# picoslidertoy.net
KiCad netlist of a schematic drawn in EAGLE
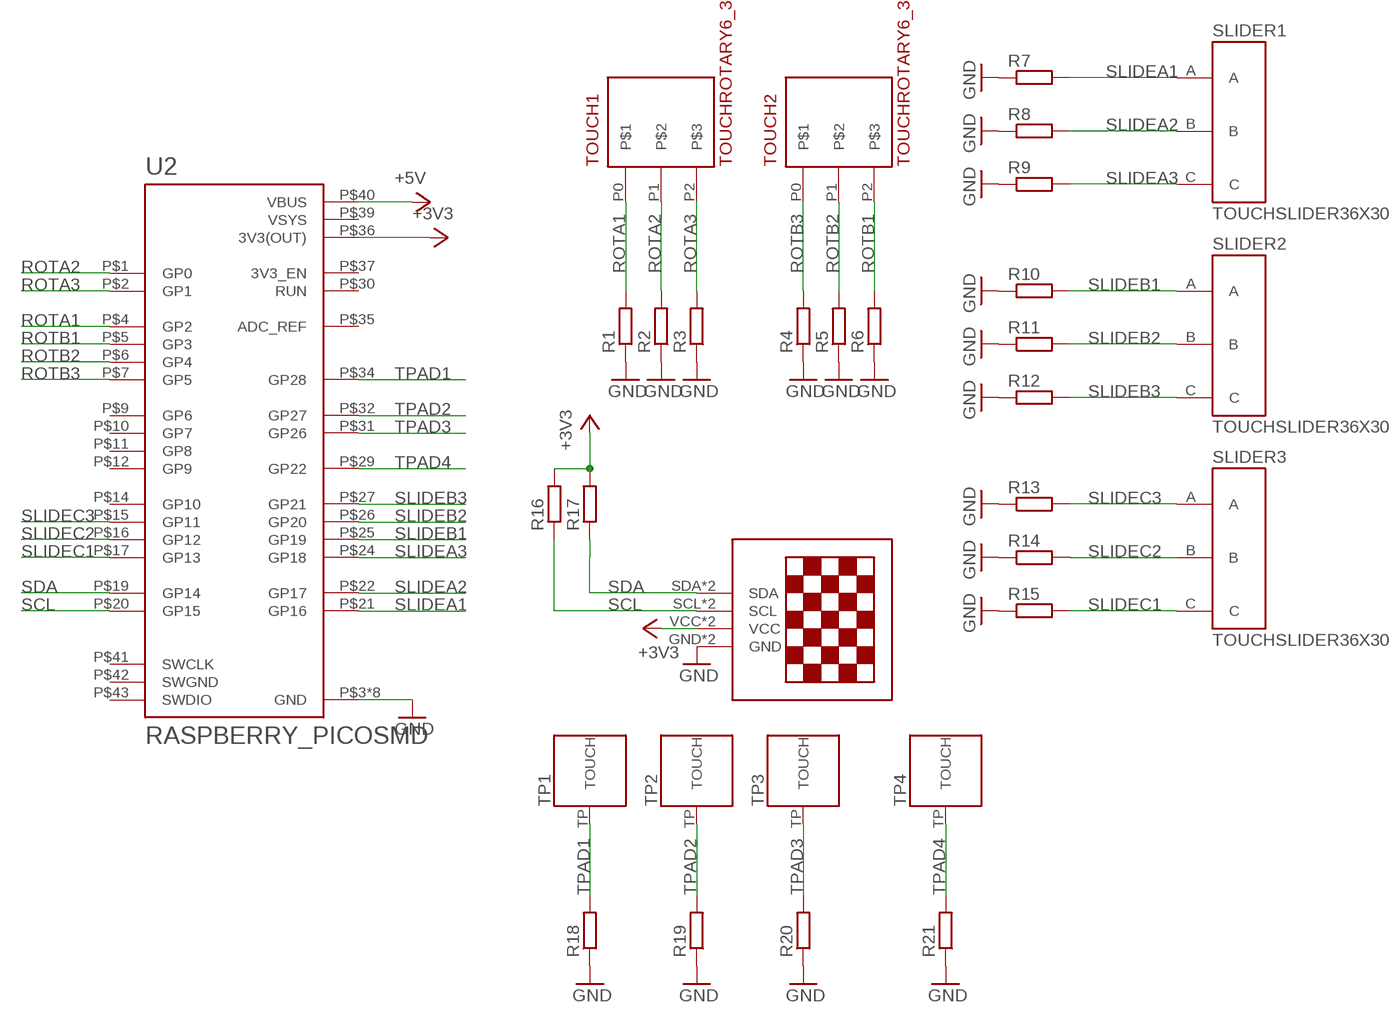
[diagram p0: schematic, sheet 1]

(export (version "E")
  (design (tool "Eeschema 10.0.6"))
  (components
    (comp (ref "R1")
      (value "R-EU_R0805")
      (footprint "eagle-import:R0805")
      (libsource (lib "eagle-import") (part "R-EU_R0805"))
    )
    (comp (ref "R2")
      (value "R-EU_R0805")
      (footprint "eagle-import:R0805")
      (libsource (lib "eagle-import") (part "R-EU_R0805"))
    )
    (comp (ref "R3")
      (value "R-EU_R0805")
      (footprint "eagle-import:R0805")
      (libsource (lib "eagle-import") (part "R-EU_R0805"))
    )
    (comp (ref "R4")
      (value "R-EU_R0805")
      (footprint "eagle-import:R0805")
      (libsource (lib "eagle-import") (part "R-EU_R0805"))
    )
    (comp (ref "R5")
      (value "R-EU_R0805")
      (footprint "eagle-import:R0805")
      (libsource (lib "eagle-import") (part "R-EU_R0805"))
    )
    (comp (ref "R6")
      (value "R-EU_R0805")
      (footprint "eagle-import:R0805")
      (libsource (lib "eagle-import") (part "R-EU_R0805"))
    )
    (comp (ref "R7")
      (value "R-EU_R0805")
      (footprint "eagle-import:R0805")
      (libsource (lib "eagle-import") (part "R-EU_R0805"))
    )
    (comp (ref "R8")
      (value "R-EU_R0805")
      (footprint "eagle-import:R0805")
      (libsource (lib "eagle-import") (part "R-EU_R0805"))
    )
    (comp (ref "R9")
      (value "R-EU_R0805")
      (footprint "eagle-import:R0805")
      (libsource (lib "eagle-import") (part "R-EU_R0805"))
    )
    (comp (ref "R10")
      (value "R-EU_R0805")
      (footprint "eagle-import:R0805")
      (libsource (lib "eagle-import") (part "R-EU_R0805"))
    )
    (comp (ref "R11")
      (value "R-EU_R0805")
      (footprint "eagle-import:R0805")
      (libsource (lib "eagle-import") (part "R-EU_R0805"))
    )
    (comp (ref "R12")
      (value "R-EU_R0805")
      (footprint "eagle-import:R0805")
      (libsource (lib "eagle-import") (part "R-EU_R0805"))
    )
    (comp (ref "R13")
      (value "R-EU_R0805")
      (footprint "eagle-import:R0805")
      (libsource (lib "eagle-import") (part "R-EU_R0805"))
    )
    (comp (ref "R14")
      (value "R-EU_R0805")
      (footprint "eagle-import:R0805")
      (libsource (lib "eagle-import") (part "R-EU_R0805"))
    )
    (comp (ref "R15")
      (value "R-EU_R0805")
      (footprint "eagle-import:R0805")
      (libsource (lib "eagle-import") (part "R-EU_R0805"))
    )
    (comp (ref "R16")
      (value "R-EU_R0805")
      (footprint "eagle-import:R0805")
      (libsource (lib "eagle-import") (part "R-EU_R0805"))
    )
    (comp (ref "R17")
      (value "R-EU_R0805")
      (footprint "eagle-import:R0805")
      (libsource (lib "eagle-import") (part "R-EU_R0805"))
    )
    (comp (ref "R18")
      (value "R-EU_R0805")
      (footprint "eagle-import:R0805")
      (libsource (lib "eagle-import") (part "R-EU_R0805"))
    )
    (comp (ref "R19")
      (value "R-EU_R0805")
      (footprint "eagle-import:R0805")
      (libsource (lib "eagle-import") (part "R-EU_R0805"))
    )
    (comp (ref "R20")
      (value "R-EU_R0805")
      (footprint "eagle-import:R0805")
      (libsource (lib "eagle-import") (part "R-EU_R0805"))
    )
    (comp (ref "R21")
      (value "R-EU_R0805")
      (footprint "eagle-import:R0805")
      (libsource (lib "eagle-import") (part "R-EU_R0805"))
    )
    (comp (ref "SLIDER1")
      (value "TOUCHSLIDER36X30")
      (footprint "eagle-import:TOUCHSLIDER3_6X30")
      (libsource (lib "eagle-import") (part "TOUCHSLIDER36X30"))
    )
    (comp (ref "SLIDER2")
      (value "TOUCHSLIDER36X30")
      (footprint "eagle-import:TOUCHSLIDER3_6X30")
      (libsource (lib "eagle-import") (part "TOUCHSLIDER36X30"))
    )
    (comp (ref "SLIDER3")
      (value "TOUCHSLIDER36X30")
      (footprint "eagle-import:TOUCHSLIDER3_6X30")
      (libsource (lib "eagle-import") (part "TOUCHSLIDER36X30"))
    )
    (comp (ref "SMDBACK2")
      (value "13\"OLED")
      (footprint "eagle-import:1.3_OLED_SMDBACK")
      (libsource (lib "eagle-import") (part "13{dblquote}OLED"))
    )
    (comp (ref "TOUCH1")
      (value "TOUCHROTARY6_30")
      (footprint "eagle-import:TOUCHROTARY1B")
      (libsource (lib "eagle-import") (part "TOUCHROTARY6_30"))
    )
    (comp (ref "TOUCH2")
      (value "TOUCHROTARY6_30")
      (footprint "eagle-import:TOUCHROTARY1B")
      (libsource (lib "eagle-import") (part "TOUCHROTARY6_30"))
    )
    (comp (ref "TP1")
      (value "TOUCHPADA")
      (footprint "eagle-import:TOUCHPADA_0.5IN")
      (libsource (lib "eagle-import") (part "TOUCHPADA"))
    )
    (comp (ref "TP2")
      (value "TOUCHPADA")
      (footprint "eagle-import:TOUCHPADA_0.5IN")
      (libsource (lib "eagle-import") (part "TOUCHPADA"))
    )
    (comp (ref "TP3")
      (value "TOUCHPADA")
      (footprint "eagle-import:TOUCHPADA_0.5IN")
      (libsource (lib "eagle-import") (part "TOUCHPADA"))
    )
    (comp (ref "TP4")
      (value "TOUCHPADA")
      (footprint "eagle-import:TOUCHPADA_0.5IN")
      (libsource (lib "eagle-import") (part "TOUCHPADA"))
    )
    (comp (ref "U2")
      (value "RASPBERRY_PICOSMD")
      (footprint "eagle-import:PICO-PKG-SMD")
      (libsource (lib "eagle-import") (part "RASPBERRY_PICOSMD"))
    )
  )
  (nets
    (net (code "1") (name "+3V3") (class "Default")
      (node (ref "R16") (pin "2") (pinfunction "2_2") (pintype "passive"))
      (node (ref "R17") (pin "2") (pinfunction "2_2") (pintype "passive"))
      (node (ref "SMDBACK2") (pin "VCC") (pinfunction "VCC_VCC") (pintype "bidirectional"))
      (node (ref "SMDBACK2") (pin "VCC_2") (pinfunction "VCC_VCC_2") (pintype "bidirectional"))
      (node (ref "U2") (pin "P$36") (pinfunction "3V3(OUT)_P$36") (pintype "power_in"))
    )
    (net (code "2") (name "+5V") (class "Default")
      (node (ref "U2") (pin "P$40") (pinfunction "VBUS_P$40") (pintype "power_in"))
    )
    (net (code "3") (name "/ROTA1") (class "Default")
      (node (ref "R1") (pin "2") (pinfunction "2_2") (pintype "passive"))
      (node (ref "TOUCH1") (pin "P0") (pinfunction "P$1_P0") (pintype "bidirectional"))
      (node (ref "U2") (pin "P$4") (pinfunction "GP2_P$4") (pintype "bidirectional"))
    )
    (net (code "4") (name "/ROTA2") (class "Default")
      (node (ref "R2") (pin "2") (pinfunction "2_2") (pintype "passive"))
      (node (ref "TOUCH1") (pin "P1") (pinfunction "P$2_P1") (pintype "bidirectional"))
      (node (ref "U2") (pin "P$1") (pinfunction "GP0_P$1") (pintype "bidirectional"))
    )
    (net (code "5") (name "/ROTA3") (class "Default")
      (node (ref "R3") (pin "2") (pinfunction "2_2") (pintype "passive"))
      (node (ref "TOUCH1") (pin "P2") (pinfunction "P$3_P2") (pintype "bidirectional"))
      (node (ref "U2") (pin "P$2") (pinfunction "GP1_P$2") (pintype "bidirectional"))
    )
    (net (code "6") (name "/ROTB1") (class "Default")
      (node (ref "R6") (pin "2") (pinfunction "2_2") (pintype "passive"))
      (node (ref "TOUCH2") (pin "P2") (pinfunction "P$3_P2") (pintype "bidirectional"))
      (node (ref "U2") (pin "P$5") (pinfunction "GP3_P$5") (pintype "bidirectional"))
    )
    (net (code "7") (name "/ROTB2") (class "Default")
      (node (ref "R5") (pin "2") (pinfunction "2_2") (pintype "passive"))
      (node (ref "TOUCH2") (pin "P1") (pinfunction "P$2_P1") (pintype "bidirectional"))
      (node (ref "U2") (pin "P$6") (pinfunction "GP4_P$6") (pintype "bidirectional"))
    )
    (net (code "8") (name "/ROTB3") (class "Default")
      (node (ref "R4") (pin "2") (pinfunction "2_2") (pintype "passive"))
      (node (ref "TOUCH2") (pin "P0") (pinfunction "P$1_P0") (pintype "bidirectional"))
      (node (ref "U2") (pin "P$7") (pinfunction "GP5_P$7") (pintype "bidirectional"))
    )
    (net (code "9") (name "/SCL") (class "Default")
      (node (ref "R16") (pin "1") (pinfunction "1_1") (pintype "passive"))
      (node (ref "SMDBACK2") (pin "SCL") (pinfunction "SCL_SCL") (pintype "bidirectional"))
      (node (ref "SMDBACK2") (pin "SCL_2") (pinfunction "SCL_SCL_2") (pintype "bidirectional"))
      (node (ref "U2") (pin "P$20") (pinfunction "GP15_P$20") (pintype "bidirectional"))
    )
    (net (code "10") (name "/SDA") (class "Default")
      (node (ref "R17") (pin "1") (pinfunction "1_1") (pintype "passive"))
      (node (ref "SMDBACK2") (pin "SDA") (pinfunction "SDA_SDA") (pintype "bidirectional"))
      (node (ref "SMDBACK2") (pin "SDA_2") (pinfunction "SDA_SDA_2") (pintype "bidirectional"))
      (node (ref "U2") (pin "P$19") (pinfunction "GP14_P$19") (pintype "bidirectional"))
    )
    (net (code "11") (name "/SLIDEA1") (class "Default")
      (node (ref "R7") (pin "2") (pinfunction "2_2") (pintype "passive"))
      (node (ref "SLIDER1") (pin "A") (pinfunction "A_A") (pintype "bidirectional"))
      (node (ref "U2") (pin "P$21") (pinfunction "GP16_P$21") (pintype "bidirectional"))
    )
    (net (code "12") (name "/SLIDEA2") (class "Default")
      (node (ref "R8") (pin "2") (pinfunction "2_2") (pintype "passive"))
      (node (ref "SLIDER1") (pin "B") (pinfunction "B_B") (pintype "bidirectional"))
      (node (ref "U2") (pin "P$22") (pinfunction "GP17_P$22") (pintype "bidirectional"))
    )
    (net (code "13") (name "/SLIDEA3") (class "Default")
      (node (ref "R9") (pin "2") (pinfunction "2_2") (pintype "passive"))
      (node (ref "SLIDER1") (pin "C") (pinfunction "C_C") (pintype "bidirectional"))
      (node (ref "U2") (pin "P$24") (pinfunction "GP18_P$24") (pintype "bidirectional"))
    )
    (net (code "14") (name "/SLIDEB1") (class "Default")
      (node (ref "R10") (pin "2") (pinfunction "2_2") (pintype "passive"))
      (node (ref "SLIDER2") (pin "A") (pinfunction "A_A") (pintype "bidirectional"))
      (node (ref "U2") (pin "P$25") (pinfunction "GP19_P$25") (pintype "bidirectional"))
    )
    (net (code "15") (name "/SLIDEB2") (class "Default")
      (node (ref "R11") (pin "2") (pinfunction "2_2") (pintype "passive"))
      (node (ref "SLIDER2") (pin "B") (pinfunction "B_B") (pintype "bidirectional"))
      (node (ref "U2") (pin "P$26") (pinfunction "GP20_P$26") (pintype "bidirectional"))
    )
    (net (code "16") (name "/SLIDEB3") (class "Default")
      (node (ref "R12") (pin "2") (pinfunction "2_2") (pintype "passive"))
      (node (ref "SLIDER2") (pin "C") (pinfunction "C_C") (pintype "bidirectional"))
      (node (ref "U2") (pin "P$27") (pinfunction "GP21_P$27") (pintype "bidirectional"))
    )
    (net (code "17") (name "/SLIDEC1") (class "Default")
      (node (ref "R15") (pin "2") (pinfunction "2_2") (pintype "passive"))
      (node (ref "SLIDER3") (pin "C") (pinfunction "C_C") (pintype "bidirectional"))
      (node (ref "U2") (pin "P$17") (pinfunction "GP13_P$17") (pintype "bidirectional"))
    )
    (net (code "18") (name "/SLIDEC2") (class "Default")
      (node (ref "R14") (pin "2") (pinfunction "2_2") (pintype "passive"))
      (node (ref "SLIDER3") (pin "B") (pinfunction "B_B") (pintype "bidirectional"))
      (node (ref "U2") (pin "P$16") (pinfunction "GP12_P$16") (pintype "bidirectional"))
    )
    (net (code "19") (name "/SLIDEC3") (class "Default")
      (node (ref "R13") (pin "2") (pinfunction "2_2") (pintype "passive"))
      (node (ref "SLIDER3") (pin "A") (pinfunction "A_A") (pintype "bidirectional"))
      (node (ref "U2") (pin "P$15") (pinfunction "GP11_P$15") (pintype "bidirectional"))
    )
    (net (code "20") (name "/SWGND") (class "Default")
      (node (ref "U2") (pin "P$42") (pinfunction "SWGND_P$42") (pintype "power_in"))
    )
    (net (code "21") (name "/TPAD1") (class "Default")
      (node (ref "R18") (pin "2") (pinfunction "2_2") (pintype "passive"))
      (node (ref "TP1") (pin "TP") (pinfunction "TOUCH_TP") (pintype "bidirectional"))
      (node (ref "U2") (pin "P$34") (pinfunction "GP28_P$34") (pintype "bidirectional"))
    )
    (net (code "22") (name "/TPAD2") (class "Default")
      (node (ref "R19") (pin "2") (pinfunction "2_2") (pintype "passive"))
      (node (ref "TP2") (pin "TP") (pinfunction "TOUCH_TP") (pintype "bidirectional"))
      (node (ref "U2") (pin "P$32") (pinfunction "GP27_P$32") (pintype "bidirectional"))
    )
    (net (code "23") (name "/TPAD3") (class "Default")
      (node (ref "R20") (pin "2") (pinfunction "2_2") (pintype "passive"))
      (node (ref "TP3") (pin "TP") (pinfunction "TOUCH_TP") (pintype "bidirectional"))
      (node (ref "U2") (pin "P$31") (pinfunction "GP26_P$31") (pintype "bidirectional"))
    )
    (net (code "24") (name "/TPAD4") (class "Default")
      (node (ref "R21") (pin "2") (pinfunction "2_2") (pintype "passive"))
      (node (ref "TP4") (pin "TP") (pinfunction "TOUCH_TP") (pintype "bidirectional"))
      (node (ref "U2") (pin "P$29") (pinfunction "GP22_P$29") (pintype "bidirectional"))
    )
    (net (code "25") (name "/VSYS") (class "Default")
      (node (ref "U2") (pin "P$39") (pinfunction "VSYS_P$39") (pintype "power_in"))
    )
    (net (code "26") (name "GND") (class "Default")
      (node (ref "R1") (pin "1") (pinfunction "1_1") (pintype "passive"))
      (node (ref "R10") (pin "1") (pinfunction "1_1") (pintype "passive"))
      (node (ref "R11") (pin "1") (pinfunction "1_1") (pintype "passive"))
      (node (ref "R12") (pin "1") (pinfunction "1_1") (pintype "passive"))
      (node (ref "R13") (pin "1") (pinfunction "1_1") (pintype "passive"))
      (node (ref "R14") (pin "1") (pinfunction "1_1") (pintype "passive"))
      (node (ref "R15") (pin "1") (pinfunction "1_1") (pintype "passive"))
      (node (ref "R18") (pin "1") (pinfunction "1_1") (pintype "passive"))
      (node (ref "R19") (pin "1") (pinfunction "1_1") (pintype "passive"))
      (node (ref "R2") (pin "1") (pinfunction "1_1") (pintype "passive"))
      (node (ref "R20") (pin "1") (pinfunction "1_1") (pintype "passive"))
      (node (ref "R21") (pin "1") (pinfunction "1_1") (pintype "passive"))
      (node (ref "R3") (pin "1") (pinfunction "1_1") (pintype "passive"))
      (node (ref "R4") (pin "1") (pinfunction "1_1") (pintype "passive"))
      (node (ref "R5") (pin "1") (pinfunction "1_1") (pintype "passive"))
      (node (ref "R6") (pin "1") (pinfunction "1_1") (pintype "passive"))
      (node (ref "R7") (pin "1") (pinfunction "1_1") (pintype "passive"))
      (node (ref "R8") (pin "1") (pinfunction "1_1") (pintype "passive"))
      (node (ref "R9") (pin "1") (pinfunction "1_1") (pintype "passive"))
      (node (ref "SMDBACK2") (pin "GND") (pinfunction "GND_GND") (pintype "bidirectional"))
      (node (ref "SMDBACK2") (pin "GND_2") (pinfunction "GND_GND_2") (pintype "bidirectional"))
      (node (ref "U2") (pin "P$13") (pinfunction "GND_P$13") (pintype "power_in"))
      (node (ref "U2") (pin "P$18") (pinfunction "GND_P$18") (pintype "power_in"))
      (node (ref "U2") (pin "P$23") (pinfunction "GND_P$23") (pintype "power_in"))
      (node (ref "U2") (pin "P$28") (pinfunction "GND_P$28") (pintype "power_in"))
      (node (ref "U2") (pin "P$3") (pinfunction "GND_P$3") (pintype "power_in"))
      (node (ref "U2") (pin "P$33") (pinfunction "GND_P$33") (pintype "power_in"))
      (node (ref "U2") (pin "P$38") (pinfunction "GND_P$38") (pintype "power_in"))
      (node (ref "U2") (pin "P$8") (pinfunction "GND_P$8") (pintype "power_in"))
    )
    (net (code "27") (name "unconnected-(U2-3V3_EN-PadP$37)") (class "Default")
      (node (ref "U2") (pin "P$37") (pinfunction "3V3_EN_P$37") (pintype "input"))
    )
    (net (code "28") (name "unconnected-(U2-ADC_REF-PadP$35)") (class "Default")
      (node (ref "U2") (pin "P$35") (pinfunction "ADC_REF_P$35") (pintype "input"))
    )
    (net (code "29") (name "unconnected-(U2-GP6-PadP$9)") (class "Default")
      (node (ref "U2") (pin "P$9") (pinfunction "GP6_P$9") (pintype "bidirectional"))
    )
    (net (code "30") (name "unconnected-(U2-GP7-PadP$10)") (class "Default")
      (node (ref "U2") (pin "P$10") (pinfunction "GP7_P$10") (pintype "bidirectional"))
    )
    (net (code "31") (name "unconnected-(U2-GP8-PadP$11)") (class "Default")
      (node (ref "U2") (pin "P$11") (pinfunction "GP8_P$11") (pintype "bidirectional"))
    )
    (net (code "32") (name "unconnected-(U2-GP9-PadP$12)") (class "Default")
      (node (ref "U2") (pin "P$12") (pinfunction "GP9_P$12") (pintype "bidirectional"))
    )
    (net (code "33") (name "unconnected-(U2-GP10-PadP$14)") (class "Default")
      (node (ref "U2") (pin "P$14") (pinfunction "GP10_P$14") (pintype "bidirectional"))
    )
    (net (code "34") (name "unconnected-(U2-RUN-PadP$30)") (class "Default")
      (node (ref "U2") (pin "P$30") (pinfunction "RUN_P$30") (pintype "input"))
    )
    (net (code "35") (name "unconnected-(U2-SWCLK-PadP$41)") (class "Default")
      (node (ref "U2") (pin "P$41") (pinfunction "SWCLK_P$41") (pintype "input"))
    )
    (net (code "36") (name "unconnected-(U2-SWDIO-PadP$43)") (class "Default")
      (node (ref "U2") (pin "P$43") (pinfunction "SWDIO_P$43") (pintype "bidirectional"))
    )
  )
)
